# Transceivers.net
KiCad netlist of a schematic drawn in Altium Designer
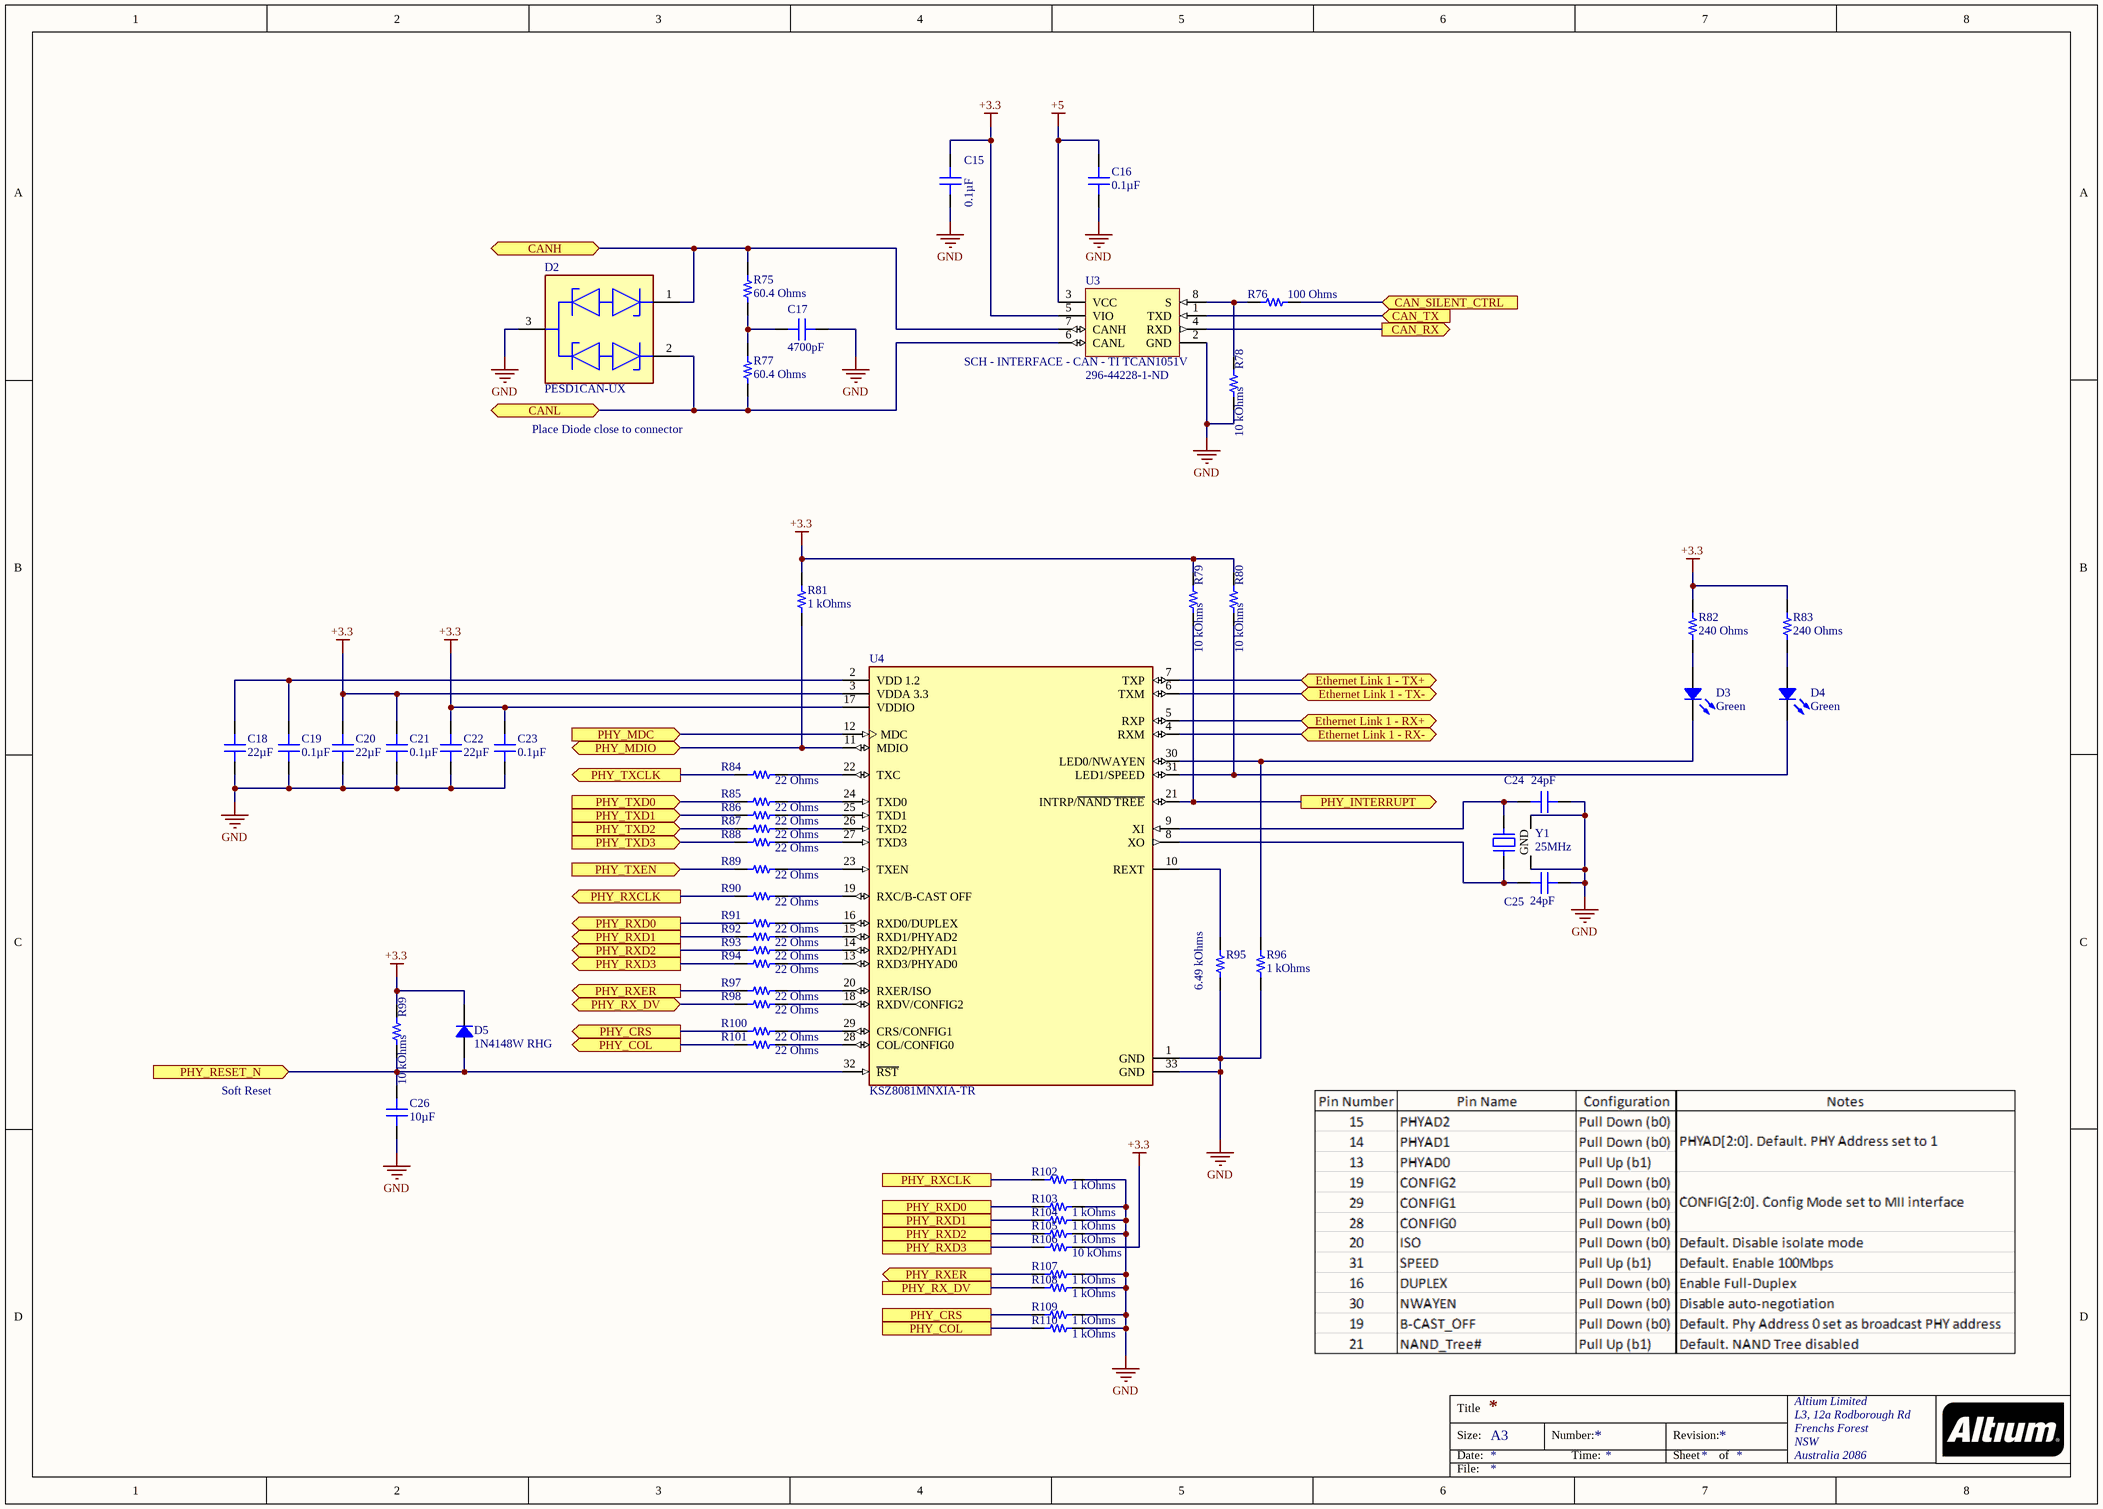
[diagram p0: Transceivers.SchDoc]

(export (version "E")
  (design (tool "Eeschema 10.0.6"))
  (components
    (comp (ref "C15")
      (value "0.1µF")
      (footprint "CAP 0603_1608")
      (description "CAP CER 0.1UF 25V X7R 0603")
      (fields
        (field (name "PART NUMBER") "CL10B104KA8WPNC")
        (field (name "MANUFACTURER") "Samsung Electro-Mechanics")
      )
      (libsource (lib "Celestial Altium Library - altium_library") (part "Capacitor"))
    )
    (comp (ref "C16")
      (value "0.1µF")
      (footprint "CAP 0603_1608")
      (description "CAP CER 0.1UF 25V X7R 0603")
      (fields
        (field (name "PART NUMBER") "CL10B104KA8WPNC")
        (field (name "MANUFACTURER") "Samsung Electro-Mechanics")
      )
      (libsource (lib "Celestial Altium Library - altium_library") (part "Capacitor"))
    )
    (comp (ref "C17")
      (value "4700pF")
      (footprint "CAP 0603_1608")
      (description "CAP CER 4700PF 50V X7R 0603")
      (fields
        (field (name "PART NUMBER") "VJ0603Y472KXACW1BC")
        (field (name "MANUFACTURER") "Vishay Vitramon")
      )
      (libsource (lib "Celestial Altium Library - altium_library") (part "Capacitor"))
    )
    (comp (ref "C18")
      (value "22µF")
      (footprint "CAP 0805_2012")
      (description "CAP CER 22UF 10V X5R 0805")
      (fields
        (field (name "PART NUMBER") "CL21A226KPCLRNC")
        (field (name "MANUFACTURER") "Samsung Electro-Mechanics")
      )
      (libsource (lib "Celestial Altium Library - altium_library") (part "Capacitor"))
    )
    (comp (ref "C19")
      (value "0.1µF")
      (footprint "CAP 0603_1608")
      (description "CAP CER 0.1UF 25V X7R 0603")
      (fields
        (field (name "PART NUMBER") "CL10B104KA8WPNC")
        (field (name "MANUFACTURER") "Samsung Electro-Mechanics")
      )
      (libsource (lib "Celestial Altium Library - altium_library") (part "Capacitor"))
    )
    (comp (ref "C20")
      (value "22µF")
      (footprint "CAP 0805_2012")
      (description "CAP CER 22UF 10V X5R 0805")
      (fields
        (field (name "PART NUMBER") "CL21A226KPCLRNC")
        (field (name "MANUFACTURER") "Samsung Electro-Mechanics")
      )
      (libsource (lib "Celestial Altium Library - altium_library") (part "Capacitor"))
    )
    (comp (ref "C21")
      (value "0.1µF")
      (footprint "CAP 0603_1608")
      (description "CAP CER 0.1UF 25V X7R 0603")
      (fields
        (field (name "PART NUMBER") "CL10B104KA8WPNC")
        (field (name "MANUFACTURER") "Samsung Electro-Mechanics")
      )
      (libsource (lib "Celestial Altium Library - altium_library") (part "Capacitor"))
    )
    (comp (ref "C22")
      (value "22µF")
      (footprint "CAP 0805_2012")
      (description "CAP CER 22UF 10V X5R 0805")
      (fields
        (field (name "PART NUMBER") "CL21A226KPCLRNC")
        (field (name "MANUFACTURER") "Samsung Electro-Mechanics")
      )
      (libsource (lib "Celestial Altium Library - altium_library") (part "Capacitor"))
    )
    (comp (ref "C23")
      (value "0.1µF")
      (footprint "CAP 0603_1608")
      (description "CAP CER 0.1UF 25V X7R 0603")
      (fields
        (field (name "PART NUMBER") "CL10B104KA8WPNC")
        (field (name "MANUFACTURER") "Samsung Electro-Mechanics")
      )
      (libsource (lib "Celestial Altium Library - altium_library") (part "Capacitor"))
    )
    (comp (ref "C24")
      (value "24pF")
      (footprint "CAP 0603_1608")
      (description "CAP CER 24PF 50V C0G/NP0 0603")
      (fields
        (field (name "PART NUMBER") "CL10C240JB8NNNC")
        (field (name "MANUFACTURER") "Samsung Electro-Mechanics")
      )
      (libsource (lib "Celestial Altium Library - altium_library") (part "Capacitor"))
    )
    (comp (ref "C25")
      (value "24pF")
      (footprint "CAP 0603_1608")
      (description "CAP CER 24PF 50V C0G/NP0 0603")
      (fields
        (field (name "PART NUMBER") "CL10C240JB8NNNC")
        (field (name "MANUFACTURER") "Samsung Electro-Mechanics")
      )
      (libsource (lib "Celestial Altium Library - altium_library") (part "Capacitor"))
    )
    (comp (ref "C26")
      (value "10µF")
      (footprint "CAP 0805_2012")
      (description "CAP CER 10UF 16V X5R 0805")
      (fields (field (name "PART NUMBER") "CC0805KKX5R7BB106") (field (name "MANUFACTURER") "Yageo"))
      (libsource (lib "Celestial Altium Library - altium_library") (part "Capacitor"))
    )
    (comp (ref "D2")
      (value "PESD1CAN-UX")
      (footprint "FP-SOT323-MFG")
      (description "TVS DIODE 24V 50V SC70-3")
      (libsource (lib "Altium Content Vault") (part "04d57993b6b7b0f5b3c95ba4f97dea0"))
    )
    (comp (ref "D3")
      (value "Green")
      (footprint "LED 0603_1608 GREEN")
      (description "LED GREEN CLEAR CHIP SMD")
      (fields (field (name "PART NUMBER") "LTST-C193KGKT-5A") (field (name "MANUFACTURER") "Lite-On Inc."))
      (libsource (lib "Celestial Altium Library - altium_library") (part "LED"))
    )
    (comp (ref "D4")
      (value "Green")
      (footprint "LED 0603_1608 GREEN")
      (description "LED GREEN CLEAR CHIP SMD")
      (fields (field (name "PART NUMBER") "LTST-C193KGKT-5A") (field (name "MANUFACTURER") "Lite-On Inc."))
      (libsource (lib "Celestial Altium Library - altium_library") (part "LED"))
    )
    (comp (ref "D5")
      (value "1N4148W RHG")
      (footprint "SOD123F")
      (description "DIODE GEN PURP 100V 150MA SOD123")
      (fields (field (name "MANUFACTURER") "Taiwan Semiconductor Corporation"))
      (libsource (lib "Celestial Altium Library - altium_library") (part "Diode"))
    )
    (comp (ref "R75")
      (value "60.4 Ohms")
      (footprint "RES 1206_3216")
      (description "RES SMD 60.4 OHM 1% 1/2W 1206")
      (fields (field (name "PART NUMBER") "ESR18EZPF60R4") (field (name "MANUFACTURER") "Rohm Semiconductor"))
      (libsource (lib "Celestial Altium Library - altium_library") (part "Resistor"))
    )
    (comp (ref "R76")
      (value "100 Ohms")
      (footprint "RES 0603_1608")
      (description "RES 100 OHM 1% 1/10W 0603")
      (fields
        (field (name "PART NUMBER") "RMCF0603FG100R")
        (field (name "MANUFACTURER") "Stackpole Electronics Inc")
      )
      (libsource (lib "Celestial Altium Library - altium_library") (part "Resistor"))
    )
    (comp (ref "R77")
      (value "60.4 Ohms")
      (footprint "RES 1206_3216")
      (description "RES SMD 60.4 OHM 1% 1/2W 1206")
      (fields (field (name "PART NUMBER") "ESR18EZPF60R4") (field (name "MANUFACTURER") "Rohm Semiconductor"))
      (libsource (lib "Celestial Altium Library - altium_library") (part "Resistor"))
    )
    (comp (ref "R78")
      (value "10 kOhms")
      (footprint "RES 0603_1608")
      (description "RES 10K OHM 5% 1/10W 0603")
      (fields
        (field (name "PART NUMBER") "RMCF0603JT10K0")
        (field (name "MANUFACTURER") "Stackpole Electronics Inc")
      )
      (libsource (lib "Celestial Altium Library - altium_library") (part "Resistor"))
    )
    (comp (ref "R79")
      (value "10 kOhms")
      (footprint "RES 0603_1608")
      (description "RES 10K OHM 5% 1/10W 0603")
      (fields
        (field (name "PART NUMBER") "RMCF0603JT10K0")
        (field (name "MANUFACTURER") "Stackpole Electronics Inc")
      )
      (libsource (lib "Celestial Altium Library - altium_library") (part "Resistor"))
    )
    (comp (ref "R80")
      (value "10 kOhms")
      (footprint "RES 0603_1608")
      (description "RES 10K OHM 5% 1/10W 0603")
      (fields
        (field (name "PART NUMBER") "RMCF0603JT10K0")
        (field (name "MANUFACTURER") "Stackpole Electronics Inc")
      )
      (libsource (lib "Celestial Altium Library - altium_library") (part "Resistor"))
    )
    (comp (ref "R81")
      (value "1 kOhms")
      (footprint "RES 0603_1608")
      (description "RES 1K OHM 1% 1/8W 0603")
      (fields
        (field (name "PART NUMBER") "RNCP0603FTD1K00")
        (field (name "MANUFACTURER") "Stackpole Electronics Inc")
      )
      (libsource (lib "Celestial Altium Library - altium_library") (part "Resistor"))
    )
    (comp (ref "R82")
      (value "240 Ohms")
      (footprint "RES 0603_1608")
      (description "RES 240 OHM 5% 1/10W 0603")
      (fields
        (field (name "PART NUMBER") "RMCF0603JT240R")
        (field (name "MANUFACTURER") "Stackpole Electronics Inc")
      )
      (libsource (lib "Celestial Altium Library - altium_library") (part "Resistor"))
    )
    (comp (ref "R83")
      (value "240 Ohms")
      (footprint "RES 0603_1608")
      (description "RES 240 OHM 5% 1/10W 0603")
      (fields
        (field (name "PART NUMBER") "RMCF0603JT240R")
        (field (name "MANUFACTURER") "Stackpole Electronics Inc")
      )
      (libsource (lib "Celestial Altium Library - altium_library") (part "Resistor"))
    )
    (comp (ref "R84")
      (value "22 Ohms")
      (footprint "RES 0603_1608")
      (description "RES 22 OHM 1% 1/10W 0603")
      (fields
        (field (name "PART NUMBER") "RMCF0603FT22R0")
        (field (name "MANUFACTURER") "Stackpole Electronics Inc")
      )
      (libsource (lib "Celestial Altium Library - altium_library") (part "Resistor"))
    )
    (comp (ref "R85")
      (value "22 Ohms")
      (footprint "RES 0603_1608")
      (description "RES 22 OHM 1% 1/10W 0603")
      (fields
        (field (name "PART NUMBER") "RMCF0603FT22R0")
        (field (name "MANUFACTURER") "Stackpole Electronics Inc")
      )
      (libsource (lib "Celestial Altium Library - altium_library") (part "Resistor"))
    )
    (comp (ref "R86")
      (value "22 Ohms")
      (footprint "RES 0603_1608")
      (description "RES 22 OHM 1% 1/10W 0603")
      (fields
        (field (name "PART NUMBER") "RMCF0603FT22R0")
        (field (name "MANUFACTURER") "Stackpole Electronics Inc")
      )
      (libsource (lib "Celestial Altium Library - altium_library") (part "Resistor"))
    )
    (comp (ref "R87")
      (value "22 Ohms")
      (footprint "RES 0603_1608")
      (description "RES 22 OHM 1% 1/10W 0603")
      (fields
        (field (name "PART NUMBER") "RMCF0603FT22R0")
        (field (name "MANUFACTURER") "Stackpole Electronics Inc")
      )
      (libsource (lib "Celestial Altium Library - altium_library") (part "Resistor"))
    )
    (comp (ref "R88")
      (value "22 Ohms")
      (footprint "RES 0603_1608")
      (description "RES 22 OHM 1% 1/10W 0603")
      (fields
        (field (name "PART NUMBER") "RMCF0603FT22R0")
        (field (name "MANUFACTURER") "Stackpole Electronics Inc")
      )
      (libsource (lib "Celestial Altium Library - altium_library") (part "Resistor"))
    )
    (comp (ref "R89")
      (value "22 Ohms")
      (footprint "RES 0603_1608")
      (description "RES 22 OHM 1% 1/10W 0603")
      (fields
        (field (name "PART NUMBER") "RMCF0603FT22R0")
        (field (name "MANUFACTURER") "Stackpole Electronics Inc")
      )
      (libsource (lib "Celestial Altium Library - altium_library") (part "Resistor"))
    )
    (comp (ref "R90")
      (value "22 Ohms")
      (footprint "RES 0603_1608")
      (description "RES 22 OHM 1% 1/10W 0603")
      (fields
        (field (name "PART NUMBER") "RMCF0603FT22R0")
        (field (name "MANUFACTURER") "Stackpole Electronics Inc")
      )
      (libsource (lib "Celestial Altium Library - altium_library") (part "Resistor"))
    )
    (comp (ref "R91")
      (value "22 Ohms")
      (footprint "RES 0603_1608")
      (description "RES 22 OHM 1% 1/10W 0603")
      (fields
        (field (name "PART NUMBER") "RMCF0603FT22R0")
        (field (name "MANUFACTURER") "Stackpole Electronics Inc")
      )
      (libsource (lib "Celestial Altium Library - altium_library") (part "Resistor"))
    )
    (comp (ref "R92")
      (value "22 Ohms")
      (footprint "RES 0603_1608")
      (description "RES 22 OHM 1% 1/10W 0603")
      (fields
        (field (name "PART NUMBER") "RMCF0603FT22R0")
        (field (name "MANUFACTURER") "Stackpole Electronics Inc")
      )
      (libsource (lib "Celestial Altium Library - altium_library") (part "Resistor"))
    )
    (comp (ref "R93")
      (value "22 Ohms")
      (footprint "RES 0603_1608")
      (description "RES 22 OHM 1% 1/10W 0603")
      (fields
        (field (name "PART NUMBER") "RMCF0603FT22R0")
        (field (name "MANUFACTURER") "Stackpole Electronics Inc")
      )
      (libsource (lib "Celestial Altium Library - altium_library") (part "Resistor"))
    )
    (comp (ref "R94")
      (value "22 Ohms")
      (footprint "RES 0603_1608")
      (description "RES 22 OHM 1% 1/10W 0603")
      (fields
        (field (name "PART NUMBER") "RMCF0603FT22R0")
        (field (name "MANUFACTURER") "Stackpole Electronics Inc")
      )
      (libsource (lib "Celestial Altium Library - altium_library") (part "Resistor"))
    )
    (comp (ref "R95")
      (value "6.49 kOhms")
      (footprint "RES 0603_1608")
      (description "RES 6.49K OHM 1% 1/8W 0603")
      (fields
        (field (name "PART NUMBER") "RNCP0603FTD6K49")
        (field (name "MANUFACTURER") "Stackpole Electronics Inc")
      )
      (libsource (lib "Celestial Altium Library - altium_library") (part "Resistor"))
    )
    (comp (ref "R96")
      (value "1 kOhms")
      (footprint "RES 0603_1608")
      (description "RES 1K OHM 1% 1/8W 0603")
      (fields
        (field (name "PART NUMBER") "RNCP0603FTD1K00")
        (field (name "MANUFACTURER") "Stackpole Electronics Inc")
      )
      (libsource (lib "Celestial Altium Library - altium_library") (part "Resistor"))
    )
    (comp (ref "R97")
      (value "22 Ohms")
      (footprint "RES 0603_1608")
      (description "RES 22 OHM 1% 1/10W 0603")
      (fields
        (field (name "PART NUMBER") "RMCF0603FT22R0")
        (field (name "MANUFACTURER") "Stackpole Electronics Inc")
      )
      (libsource (lib "Celestial Altium Library - altium_library") (part "Resistor"))
    )
    (comp (ref "R98")
      (value "22 Ohms")
      (footprint "RES 0603_1608")
      (description "RES 22 OHM 1% 1/10W 0603")
      (fields
        (field (name "PART NUMBER") "RMCF0603FT22R0")
        (field (name "MANUFACTURER") "Stackpole Electronics Inc")
      )
      (libsource (lib "Celestial Altium Library - altium_library") (part "Resistor"))
    )
    (comp (ref "R99")
      (value "10 kOhms")
      (footprint "RES 0603_1608")
      (description "RES 10K OHM 5% 1/10W 0603")
      (fields
        (field (name "PART NUMBER") "RMCF0603JT10K0")
        (field (name "MANUFACTURER") "Stackpole Electronics Inc")
      )
      (libsource (lib "Celestial Altium Library - altium_library") (part "Resistor"))
    )
    (comp (ref "R100")
      (value "22 Ohms")
      (footprint "RES 0603_1608")
      (description "RES 22 OHM 1% 1/10W 0603")
      (fields
        (field (name "PART NUMBER") "RMCF0603FT22R0")
        (field (name "MANUFACTURER") "Stackpole Electronics Inc")
      )
      (libsource (lib "Celestial Altium Library - altium_library") (part "Resistor"))
    )
    (comp (ref "R101")
      (value "22 Ohms")
      (footprint "RES 0603_1608")
      (description "RES 22 OHM 1% 1/10W 0603")
      (fields
        (field (name "PART NUMBER") "RMCF0603FT22R0")
        (field (name "MANUFACTURER") "Stackpole Electronics Inc")
      )
      (libsource (lib "Celestial Altium Library - altium_library") (part "Resistor"))
    )
    (comp (ref "R102")
      (value "1 kOhms")
      (footprint "RES 0603_1608")
      (description "RES 1K OHM 1% 1/8W 0603")
      (fields
        (field (name "PART NUMBER") "RNCP0603FTD1K00")
        (field (name "MANUFACTURER") "Stackpole Electronics Inc")
      )
      (libsource (lib "Celestial Altium Library - altium_library") (part "Resistor"))
    )
    (comp (ref "R103")
      (value "1 kOhms")
      (footprint "RES 0603_1608")
      (description "RES 1K OHM 1% 1/8W 0603")
      (fields
        (field (name "PART NUMBER") "RNCP0603FTD1K00")
        (field (name "MANUFACTURER") "Stackpole Electronics Inc")
      )
      (libsource (lib "Celestial Altium Library - altium_library") (part "Resistor"))
    )
    (comp (ref "R104")
      (value "1 kOhms")
      (footprint "RES 0603_1608")
      (description "RES 1K OHM 1% 1/8W 0603")
      (fields
        (field (name "PART NUMBER") "RNCP0603FTD1K00")
        (field (name "MANUFACTURER") "Stackpole Electronics Inc")
      )
      (libsource (lib "Celestial Altium Library - altium_library") (part "Resistor"))
    )
    (comp (ref "R105")
      (value "1 kOhms")
      (footprint "RES 0603_1608")
      (description "RES 1K OHM 1% 1/8W 0603")
      (fields
        (field (name "PART NUMBER") "RNCP0603FTD1K00")
        (field (name "MANUFACTURER") "Stackpole Electronics Inc")
      )
      (libsource (lib "Celestial Altium Library - altium_library") (part "Resistor"))
    )
    (comp (ref "R106")
      (value "10 kOhms")
      (footprint "RES 0603_1608")
      (description "RES 10K OHM 5% 1/10W 0603")
      (fields
        (field (name "PART NUMBER") "RMCF0603JT10K0")
        (field (name "MANUFACTURER") "Stackpole Electronics Inc")
      )
      (libsource (lib "Celestial Altium Library - altium_library") (part "Resistor"))
    )
    (comp (ref "R107")
      (value "1 kOhms")
      (footprint "RES 0603_1608")
      (description "RES 1K OHM 1% 1/8W 0603")
      (fields
        (field (name "PART NUMBER") "RNCP0603FTD1K00")
        (field (name "MANUFACTURER") "Stackpole Electronics Inc")
      )
      (libsource (lib "Celestial Altium Library - altium_library") (part "Resistor"))
    )
    (comp (ref "R108")
      (value "1 kOhms")
      (footprint "RES 0603_1608")
      (description "RES 1K OHM 1% 1/8W 0603")
      (fields
        (field (name "PART NUMBER") "RNCP0603FTD1K00")
        (field (name "MANUFACTURER") "Stackpole Electronics Inc")
      )
      (libsource (lib "Celestial Altium Library - altium_library") (part "Resistor"))
    )
    (comp (ref "R109")
      (value "1 kOhms")
      (footprint "RES 0603_1608")
      (description "RES 1K OHM 1% 1/8W 0603")
      (fields
        (field (name "PART NUMBER") "RNCP0603FTD1K00")
        (field (name "MANUFACTURER") "Stackpole Electronics Inc")
      )
      (libsource (lib "Celestial Altium Library - altium_library") (part "Resistor"))
    )
    (comp (ref "R110")
      (value "1 kOhms")
      (footprint "RES 0603_1608")
      (description "RES 1K OHM 1% 1/8W 0603")
      (fields
        (field (name "PART NUMBER") "RNCP0603FTD1K00")
        (field (name "MANUFACTURER") "Stackpole Electronics Inc")
      )
      (libsource (lib "Celestial Altium Library - altium_library") (part "Resistor"))
    )
    (comp (ref "U3")
      (value "SCH - INTERFACE - CAN - TI TCAN1051V")
      (footprint "PCB - LEADS - SOIC - TI SOIC-8")
      (fields (field (name "SUPPLIER PART NUMBER 1") "296-44228-1-ND"))
      (libsource (lib "HAB_ICs") (part "SCH - INTERFACE - CAN - TI TCAN1051V"))
    )
    (comp (ref "U4")
      (value "KSZ8081MNXIA-TR")
      (footprint "FP-QFN55-32LD-PL-5-MFG")
      (description "IC TRANSCEIVER FULL 1/1 32QFN")
      (fields
        (field (name "OCTOPART") "https://octopart.com/ksz8081mnxia-tr-microchip-66799958")
        (field (name "MANUFACTURER") "Microchip")
      )
      (libsource (lib "Altium Content Vault") (part "882547a6550c82911a23300368c51e3"))
    )
    (comp (ref "Y1")
      (value "25MHz")
      (footprint "EPSON TSX-3225")
      (description "CRYSTAL 25.0000MHZ 18PF SMD")
      (fields (field (name "PART NUMBER") "TSX-3225 25.0000MF20P-C0") (field (name "MANUFACTURER") "EPSON"))
      (libsource (lib "Celestial Altium Library - altium_library") (part "Epson Crystal TSX-3225"))
    )
  )
  (nets
    (net (code "1") (name "+3.3") (class "Default")
      (node (ref "C15") (pin "2") (pinfunction "2_2") (pintype "passive"))
      (node (ref "C20") (pin "2") (pinfunction "2_2") (pintype "passive"))
      (node (ref "C21") (pin "2") (pinfunction "2_2") (pintype "passive"))
      (node (ref "C22") (pin "2") (pinfunction "2_2") (pintype "passive"))
      (node (ref "C23") (pin "2") (pinfunction "2_2") (pintype "passive"))
      (node (ref "D5") (pin "2") (pinfunction "2_2") (pintype "passive"))
      (node (ref "R106") (pin "1") (pinfunction "1_1") (pintype "passive"))
      (node (ref "R79") (pin "2") (pinfunction "2_2") (pintype "passive"))
      (node (ref "R80") (pin "2") (pinfunction "2_2") (pintype "passive"))
      (node (ref "R81") (pin "2") (pinfunction "2_2") (pintype "passive"))
      (node (ref "R82") (pin "2") (pinfunction "2_2") (pintype "passive"))
      (node (ref "R83") (pin "2") (pinfunction "2_2") (pintype "passive"))
      (node (ref "R99") (pin "2") (pinfunction "2_2") (pintype "passive"))
      (node (ref "U3") (pin "5") (pinfunction "VIO_5") (pintype "power_in"))
      (node (ref "U4") (pin "17") (pinfunction "VDDIO_17") (pintype "power_in"))
      (node (ref "U4") (pin "3") (pinfunction "VDDA_3.3_3") (pintype "power_in"))
    )
    (net (code "2") (name "+5") (class "Default")
      (node (ref "C16") (pin "2") (pinfunction "2_2") (pintype "passive"))
      (node (ref "U3") (pin "3") (pinfunction "VCC_3") (pintype "power_in"))
    )
    (net (code "3") (name "/CANH") (class "Default")
      (node (ref "D2") (pin "1") (pinfunction "cathode_1_1") (pintype "passive"))
      (node (ref "R75") (pin "2") (pinfunction "2_2") (pintype "passive"))
      (node (ref "U3") (pin "7") (pinfunction "CANH_7") (pintype "bidirectional"))
    )
    (net (code "4") (name "/CANL") (class "Default")
      (node (ref "D2") (pin "2") (pinfunction "cathode_2_2") (pintype "passive"))
      (node (ref "R77") (pin "1") (pinfunction "1_1") (pintype "passive"))
      (node (ref "U3") (pin "6") (pinfunction "CANL_6") (pintype "bidirectional"))
    )
    (net (code "5") (name "/CAN_RX") (class "Default")
      (node (ref "U3") (pin "4") (pinfunction "RXD_4") (pintype "output"))
    )
    (net (code "6") (name "/CAN_SILENT_CTRL") (class "Default")
      (node (ref "R76") (pin "2") (pinfunction "2_2") (pintype "passive"))
    )
    (net (code "7") (name "/CAN_TX") (class "Default")
      (node (ref "U3") (pin "1") (pinfunction "TXD_1") (pintype "input"))
    )
    (net (code "8") (name "/Ethernet Link 1 - RX+") (class "Default")
      (node (ref "U4") (pin "5") (pinfunction "RXP_5") (pintype "bidirectional"))
    )
    (net (code "9") (name "/Ethernet Link 1 - RX-") (class "Default")
      (node (ref "U4") (pin "4") (pinfunction "RXM_4") (pintype "bidirectional"))
    )
    (net (code "10") (name "/Ethernet Link 1 - TX+") (class "Default")
      (node (ref "U4") (pin "7") (pinfunction "TXP_7") (pintype "bidirectional"))
    )
    (net (code "11") (name "/Ethernet Link 1 - TX-") (class "Default")
      (node (ref "U4") (pin "6") (pinfunction "TXM_6") (pintype "bidirectional"))
    )
    (net (code "12") (name "/PHY_COL") (class "Default")
      (node (ref "R101") (pin "1") (pinfunction "1_1") (pintype "passive"))
      (node (ref "R110") (pin "2") (pinfunction "2_2") (pintype "passive"))
    )
    (net (code "13") (name "/PHY_CRS") (class "Default")
      (node (ref "R100") (pin "1") (pinfunction "1_1") (pintype "passive"))
      (node (ref "R109") (pin "2") (pinfunction "2_2") (pintype "passive"))
    )
    (net (code "14") (name "/PHY_INTERRUPT") (class "Default")
      (node (ref "R79") (pin "1") (pinfunction "1_1") (pintype "passive"))
      (node (ref "U4") (pin "21") (pinfunction "INTRP/~{NAND_TREE}_21") (pintype "bidirectional"))
    )
    (net (code "15") (name "/PHY_MDC") (class "Default")
      (node (ref "U4") (pin "12") (pinfunction "MDC_12") (pintype "input"))
    )
    (net (code "16") (name "/PHY_MDIO") (class "Default")
      (node (ref "R81") (pin "1") (pinfunction "1_1") (pintype "passive"))
      (node (ref "U4") (pin "11") (pinfunction "MDIO_11") (pintype "bidirectional"))
    )
    (net (code "17") (name "/PHY_RESET_N") (class "Default")
      (node (ref "C26") (pin "2") (pinfunction "2_2") (pintype "passive"))
      (node (ref "D5") (pin "1") (pinfunction "1_1") (pintype "passive"))
      (node (ref "R99") (pin "1") (pinfunction "1_1") (pintype "passive"))
      (node (ref "U4") (pin "32") (pinfunction "~{RST}_32") (pintype "input"))
    )
    (net (code "18") (name "/PHY_RXCLK") (class "Default")
      (node (ref "R102") (pin "2") (pinfunction "2_2") (pintype "passive"))
      (node (ref "R90") (pin "1") (pinfunction "1_1") (pintype "passive"))
    )
    (net (code "19") (name "/PHY_RXD0") (class "Default")
      (node (ref "R103") (pin "2") (pinfunction "2_2") (pintype "passive"))
      (node (ref "R91") (pin "1") (pinfunction "1_1") (pintype "passive"))
    )
    (net (code "20") (name "/PHY_RXD1") (class "Default")
      (node (ref "R104") (pin "2") (pinfunction "2_2") (pintype "passive"))
      (node (ref "R92") (pin "1") (pinfunction "1_1") (pintype "passive"))
    )
    (net (code "21") (name "/PHY_RXD2") (class "Default")
      (node (ref "R105") (pin "2") (pinfunction "2_2") (pintype "passive"))
      (node (ref "R93") (pin "1") (pinfunction "1_1") (pintype "passive"))
    )
    (net (code "22") (name "/PHY_RXD3") (class "Default")
      (node (ref "R106") (pin "2") (pinfunction "2_2") (pintype "passive"))
      (node (ref "R94") (pin "1") (pinfunction "1_1") (pintype "passive"))
    )
    (net (code "23") (name "/PHY_RXER") (class "Default")
      (node (ref "R107") (pin "2") (pinfunction "2_2") (pintype "passive"))
      (node (ref "R97") (pin "1") (pinfunction "1_1") (pintype "passive"))
    )
    (net (code "24") (name "/PHY_RX_DV") (class "Default")
      (node (ref "R108") (pin "2") (pinfunction "2_2") (pintype "passive"))
      (node (ref "R98") (pin "1") (pinfunction "1_1") (pintype "passive"))
    )
    (net (code "25") (name "/PHY_TXCLK") (class "Default")
      (node (ref "R84") (pin "1") (pinfunction "1_1") (pintype "passive"))
    )
    (net (code "26") (name "/PHY_TXD0") (class "Default")
      (node (ref "R85") (pin "1") (pinfunction "1_1") (pintype "passive"))
    )
    (net (code "27") (name "/PHY_TXD1") (class "Default")
      (node (ref "R86") (pin "1") (pinfunction "1_1") (pintype "passive"))
    )
    (net (code "28") (name "/PHY_TXD2") (class "Default")
      (node (ref "R87") (pin "1") (pinfunction "1_1") (pintype "passive"))
    )
    (net (code "29") (name "/PHY_TXD3") (class "Default")
      (node (ref "R88") (pin "1") (pinfunction "1_1") (pintype "passive"))
    )
    (net (code "30") (name "/PHY_TXEN") (class "Default")
      (node (ref "R89") (pin "1") (pinfunction "1_1") (pintype "passive"))
    )
    (net (code "31") (name "GND") (class "Default")
      (node (ref "C15") (pin "1") (pinfunction "1_1") (pintype "passive"))
      (node (ref "C16") (pin "1") (pinfunction "1_1") (pintype "passive"))
      (node (ref "C17") (pin "2") (pinfunction "2_2") (pintype "passive"))
      (node (ref "C18") (pin "1") (pinfunction "1_1") (pintype "passive"))
      (node (ref "C19") (pin "1") (pinfunction "1_1") (pintype "passive"))
      (node (ref "C20") (pin "1") (pinfunction "1_1") (pintype "passive"))
      (node (ref "C21") (pin "1") (pinfunction "1_1") (pintype "passive"))
      (node (ref "C22") (pin "1") (pinfunction "1_1") (pintype "passive"))
      (node (ref "C23") (pin "1") (pinfunction "1_1") (pintype "passive"))
      (node (ref "C24") (pin "2") (pinfunction "2_2") (pintype "passive"))
      (node (ref "C25") (pin "2") (pinfunction "2_2") (pintype "passive"))
      (node (ref "C26") (pin "1") (pinfunction "1_1") (pintype "passive"))
      (node (ref "D2") (pin "3") (pinfunction "common_cathode_3") (pintype "passive"))
      (node (ref "R102") (pin "1") (pinfunction "1_1") (pintype "passive"))
      (node (ref "R103") (pin "1") (pinfunction "1_1") (pintype "passive"))
      (node (ref "R104") (pin "1") (pinfunction "1_1") (pintype "passive"))
      (node (ref "R105") (pin "1") (pinfunction "1_1") (pintype "passive"))
      (node (ref "R107") (pin "1") (pinfunction "1_1") (pintype "passive"))
      (node (ref "R108") (pin "1") (pinfunction "1_1") (pintype "passive"))
      (node (ref "R109") (pin "1") (pinfunction "1_1") (pintype "passive"))
      (node (ref "R110") (pin "1") (pinfunction "1_1") (pintype "passive"))
      (node (ref "R78") (pin "1") (pinfunction "1_1") (pintype "passive"))
      (node (ref "R95") (pin "1") (pinfunction "1_1") (pintype "passive"))
      (node (ref "R96") (pin "1") (pinfunction "1_1") (pintype "passive"))
      (node (ref "U3") (pin "2") (pinfunction "GND_2") (pintype "power_in"))
      (node (ref "U4") (pin "1") (pinfunction "GND_1") (pintype "power_in"))
      (node (ref "U4") (pin "33") (pinfunction "GND_33") (pintype "power_in"))
      (node (ref "Y1") (pin "2") (pinfunction "GND_2") (pintype "passive"))
      (node (ref "Y1") (pin "4") (pinfunction "GND_4") (pintype "passive"))
    )
    (net (code "32") (name "Net-(C17-Pad1)") (class "Default")
      (node (ref "C17") (pin "1") (pinfunction "1_1") (pintype "passive"))
      (node (ref "R75") (pin "1") (pinfunction "1_1") (pintype "passive"))
      (node (ref "R77") (pin "2") (pinfunction "2_2") (pintype "passive"))
    )
    (net (code "33") (name "Net-(D3-Pad1)") (class "Default")
      (node (ref "D3") (pin "1") (pinfunction "1_1") (pintype "passive"))
      (node (ref "R82") (pin "1") (pinfunction "1_1") (pintype "passive"))
    )
    (net (code "34") (name "Net-(D4-Pad1)") (class "Default")
      (node (ref "D4") (pin "1") (pinfunction "1_1") (pintype "passive"))
      (node (ref "R83") (pin "1") (pinfunction "1_1") (pintype "passive"))
    )
    (net (code "35") (name "Net-(U3-S)") (class "Default")
      (node (ref "R76") (pin "1") (pinfunction "1_1") (pintype "passive"))
      (node (ref "R78") (pin "2") (pinfunction "2_2") (pintype "passive"))
      (node (ref "U3") (pin "8") (pinfunction "S_8") (pintype "input"))
    )
    (net (code "36") (name "Net-(U4-COL{slash}CONFIG0)") (class "Default")
      (node (ref "R101") (pin "2") (pinfunction "2_2") (pintype "passive"))
      (node (ref "U4") (pin "28") (pinfunction "COL/CONFIG0_28") (pintype "bidirectional"))
    )
    (net (code "37") (name "Net-(U4-CRS{slash}CONFIG1)") (class "Default")
      (node (ref "R100") (pin "2") (pinfunction "2_2") (pintype "passive"))
      (node (ref "U4") (pin "29") (pinfunction "CRS/CONFIG1_29") (pintype "bidirectional"))
    )
    (net (code "38") (name "Net-(U4-LED0{slash}NWAYEN)") (class "Default")
      (node (ref "D3") (pin "2") (pinfunction "2_2") (pintype "passive"))
      (node (ref "R96") (pin "2") (pinfunction "2_2") (pintype "passive"))
      (node (ref "U4") (pin "30") (pinfunction "LED0/NWAYEN_30") (pintype "bidirectional"))
    )
    (net (code "39") (name "Net-(U4-LED1{slash}SPEED)") (class "Default")
      (node (ref "D4") (pin "2") (pinfunction "2_2") (pintype "passive"))
      (node (ref "R80") (pin "1") (pinfunction "1_1") (pintype "passive"))
      (node (ref "U4") (pin "31") (pinfunction "LED1/SPEED_31") (pintype "bidirectional"))
    )
    (net (code "40") (name "Net-(U4-REXT)") (class "Default")
      (node (ref "R95") (pin "2") (pinfunction "2_2") (pintype "passive"))
      (node (ref "U4") (pin "10") (pinfunction "REXT_10") (pintype "passive"))
    )
    (net (code "41") (name "Net-(U4-RXC{slash}B-CAST_OFF)") (class "Default")
      (node (ref "R90") (pin "2") (pinfunction "2_2") (pintype "passive"))
      (node (ref "U4") (pin "19") (pinfunction "RXC/B-CAST_OFF_19") (pintype "bidirectional"))
    )
    (net (code "42") (name "Net-(U4-RXD0{slash}DUPLEX)") (class "Default")
      (node (ref "R91") (pin "2") (pinfunction "2_2") (pintype "passive"))
      (node (ref "U4") (pin "16") (pinfunction "RXD0/DUPLEX_16") (pintype "bidirectional"))
    )
    (net (code "43") (name "Net-(U4-RXD1{slash}PHYAD2)") (class "Default")
      (node (ref "R92") (pin "2") (pinfunction "2_2") (pintype "passive"))
      (node (ref "U4") (pin "15") (pinfunction "RXD1/PHYAD2_15") (pintype "bidirectional"))
    )
    (net (code "44") (name "Net-(U4-RXD2{slash}PHYAD1)") (class "Default")
      (node (ref "R93") (pin "2") (pinfunction "2_2") (pintype "passive"))
      (node (ref "U4") (pin "14") (pinfunction "RXD2/PHYAD1_14") (pintype "bidirectional"))
    )
    (net (code "45") (name "Net-(U4-RXD3{slash}PHYAD0)") (class "Default")
      (node (ref "R94") (pin "2") (pinfunction "2_2") (pintype "passive"))
      (node (ref "U4") (pin "13") (pinfunction "RXD3/PHYAD0_13") (pintype "bidirectional"))
    )
    (net (code "46") (name "Net-(U4-RXDV{slash}CONFIG2)") (class "Default")
      (node (ref "R98") (pin "2") (pinfunction "2_2") (pintype "passive"))
      (node (ref "U4") (pin "18") (pinfunction "RXDV/CONFIG2_18") (pintype "bidirectional"))
    )
    (net (code "47") (name "Net-(U4-RXER{slash}ISO)") (class "Default")
      (node (ref "R97") (pin "2") (pinfunction "2_2") (pintype "passive"))
      (node (ref "U4") (pin "20") (pinfunction "RXER/ISO_20") (pintype "bidirectional"))
    )
    (net (code "48") (name "Net-(U4-TXC)") (class "Default")
      (node (ref "R84") (pin "2") (pinfunction "2_2") (pintype "passive"))
      (node (ref "U4") (pin "22") (pinfunction "TXC_22") (pintype "bidirectional"))
    )
    (net (code "49") (name "Net-(U4-TXD0)") (class "Default")
      (node (ref "R85") (pin "2") (pinfunction "2_2") (pintype "passive"))
      (node (ref "U4") (pin "24") (pinfunction "TXD0_24") (pintype "input"))
    )
    (net (code "50") (name "Net-(U4-TXD1)") (class "Default")
      (node (ref "R86") (pin "2") (pinfunction "2_2") (pintype "passive"))
      (node (ref "U4") (pin "25") (pinfunction "TXD1_25") (pintype "input"))
    )
    (net (code "51") (name "Net-(U4-TXD2)") (class "Default")
      (node (ref "R87") (pin "2") (pinfunction "2_2") (pintype "passive"))
      (node (ref "U4") (pin "26") (pinfunction "TXD2_26") (pintype "input"))
    )
    (net (code "52") (name "Net-(U4-TXD3)") (class "Default")
      (node (ref "R88") (pin "2") (pinfunction "2_2") (pintype "passive"))
      (node (ref "U4") (pin "27") (pinfunction "TXD3_27") (pintype "input"))
    )
    (net (code "53") (name "Net-(U4-TXEN)") (class "Default")
      (node (ref "R89") (pin "2") (pinfunction "2_2") (pintype "passive"))
      (node (ref "U4") (pin "23") (pinfunction "TXEN_23") (pintype "input"))
    )
    (net (code "54") (name "Net-(U4-VDD_1.2)") (class "Default")
      (node (ref "C18") (pin "2") (pinfunction "2_2") (pintype "passive"))
      (node (ref "C19") (pin "2") (pinfunction "2_2") (pintype "passive"))
      (node (ref "U4") (pin "2") (pinfunction "VDD_1.2_2") (pintype "power_in"))
    )
    (net (code "55") (name "Net-(U4-XI)") (class "Default")
      (node (ref "C24") (pin "1") (pinfunction "1_1") (pintype "passive"))
      (node (ref "U4") (pin "9") (pinfunction "XI_9") (pintype "input"))
      (node (ref "Y1") (pin "3") (pinfunction "3_3") (pintype "passive"))
    )
    (net (code "56") (name "Net-(U4-XO)") (class "Default")
      (node (ref "C25") (pin "1") (pinfunction "1_1") (pintype "passive"))
      (node (ref "U4") (pin "8") (pinfunction "XO_8") (pintype "output"))
      (node (ref "Y1") (pin "1") (pinfunction "1_1") (pintype "passive"))
    )
  )
)
